# ble_car_cent_01.net
KiCad netlist of a schematic drawn in EasyEDA
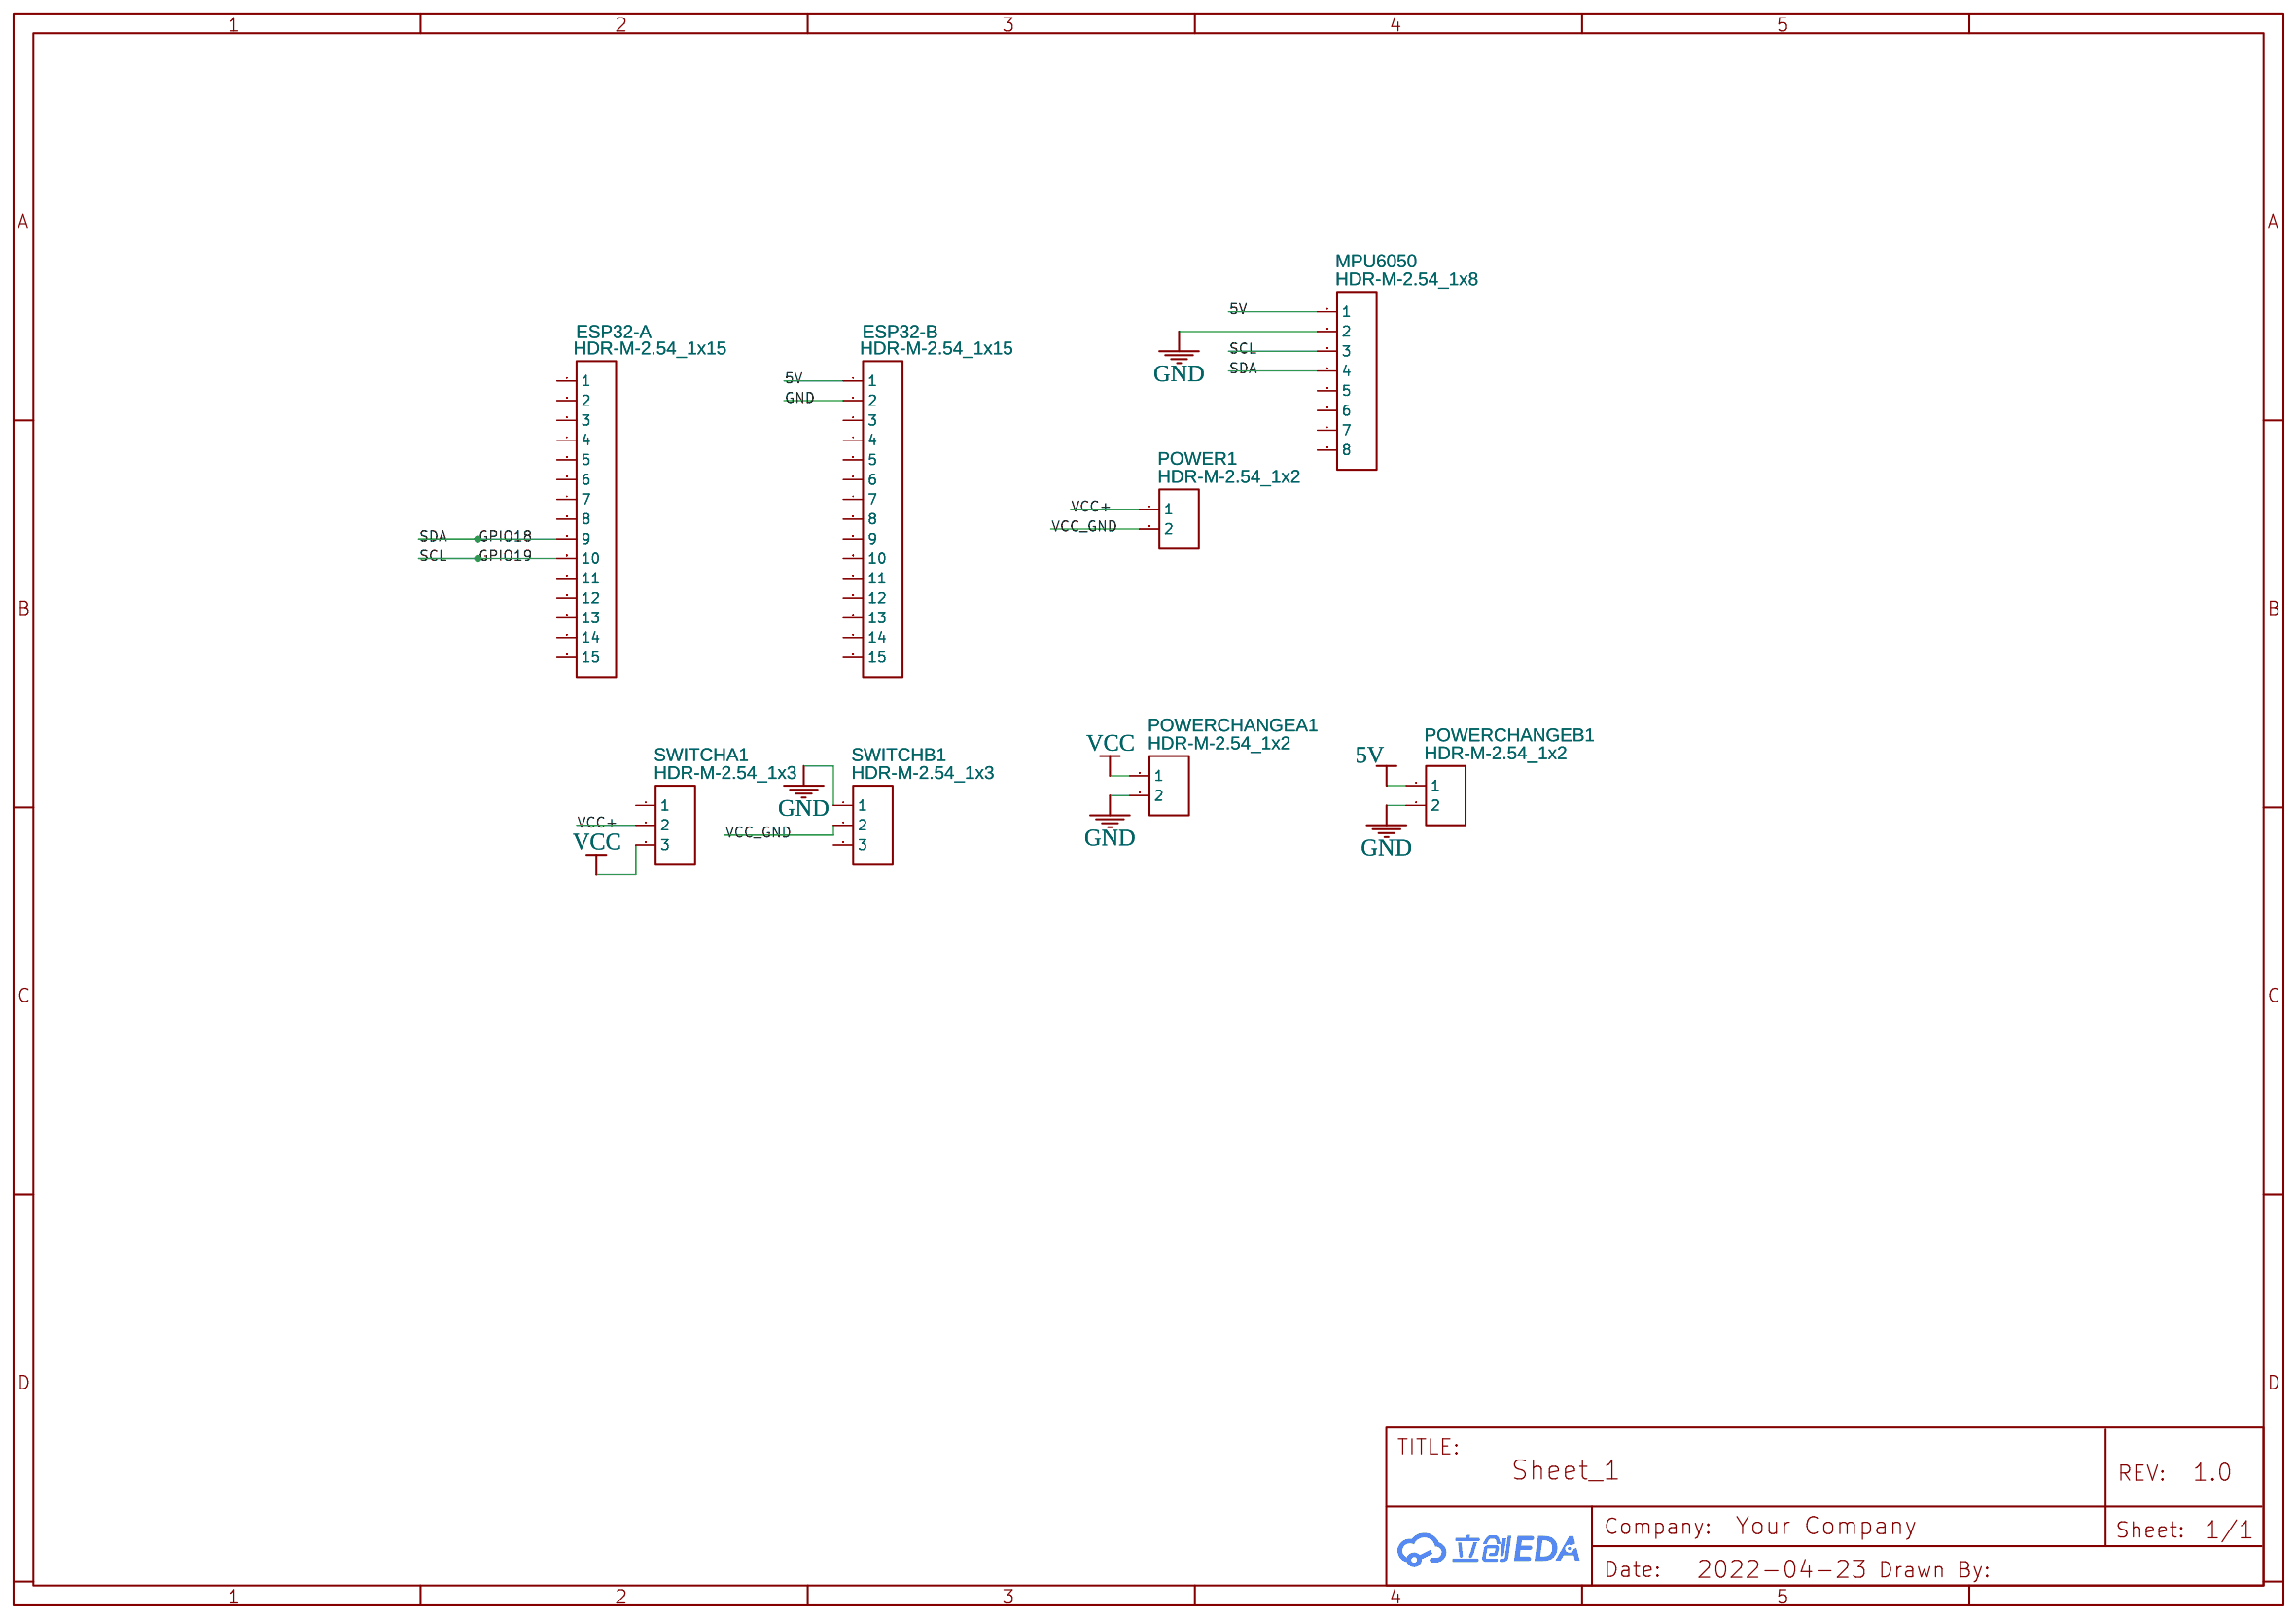
[diagram p0: schematic sheet]

(export (version "E")
  (design (tool "Eeschema 10.0.6"))
  (components
    (comp (ref "ESP32-A")
      (value "HDR-M-2.54_1x15")
      (fields (field (name "BOM_Supplier Part") "C124373"))
      (libsource (lib "") (part "HDR-M-2.54_1x15_1"))
    )
    (comp (ref "ESP32-B")
      (value "HDR-M-2.54_1x15")
      (fields (field (name "BOM_Supplier Part") "C124373"))
      (libsource (lib "") (part "HDR-M-2.54_1x15"))
    )
    (comp (ref "MPU6050")
      (value "HDR-M-2.54_1x8")
      (fields (field (name "BOM_Supplier Part") "C190820"))
      (libsource (lib "") (part "HDR-M-2.54_1x8"))
    )
    (comp (ref "POWER1")
      (value "HDR-M-2.54_1x2")
      (fields (field (name "BOM_Supplier Part") "C124375"))
      (libsource (lib "") (part "HDR-M-2.54_1x2"))
    )
    (comp (ref "POWERCHANGEA1")
      (value "HDR-M-2.54_1x2")
      (fields (field (name "BOM_Supplier Part") "C124375"))
      (libsource (lib "") (part "HDR-M-2.54_1x2_2"))
    )
    (comp (ref "POWERCHANGEB1")
      (value "HDR-M-2.54_1x2")
      (fields (field (name "BOM_Supplier Part") "C124375"))
      (libsource (lib "") (part "HDR-M-2.54_1x2_1"))
    )
    (comp (ref "SWITCHA1")
      (value "HDR-M-2.54_1x3")
      (fields (field (name "BOM_Supplier Part") "C180248"))
      (libsource (lib "") (part "HDR-M-2.54_1x3_1"))
    )
    (comp (ref "SWITCHB1")
      (value "HDR-M-2.54_1x3")
      (fields (field (name "BOM_Supplier Part") "C180248"))
      (libsource (lib "") (part "HDR-M-2.54_1x3"))
    )
  )
  (nets
    (net (code "1") (name "/GPIO18") (class "Default")
      (node (ref "ESP32-A") (pin "9") (pinfunction "9_9") (pintype "unspecified"))
      (node (ref "MPU6050") (pin "4") (pinfunction "4_4") (pintype "unspecified"))
    )
    (net (code "2") (name "/GPIO19") (class "Default")
      (node (ref "ESP32-A") (pin "10") (pinfunction "10_10") (pintype "unspecified"))
      (node (ref "MPU6050") (pin "3") (pinfunction "3_3") (pintype "unspecified"))
    )
    (net (code "3") (name "/VCC+") (class "Default")
      (node (ref "POWER1") (pin "1") (pinfunction "1_1") (pintype "unspecified"))
      (node (ref "SWITCHA1") (pin "2") (pinfunction "2_2") (pintype "input"))
    )
    (net (code "4") (name "/VCC_GND") (class "Default")
      (node (ref "POWER1") (pin "2") (pinfunction "2_2") (pintype "unspecified"))
      (node (ref "SWITCHB1") (pin "2") (pinfunction "2_2") (pintype "input"))
    )
    (net (code "5") (name "5V") (class "Default")
      (node (ref "ESP32-B") (pin "1") (pinfunction "1_1") (pintype "unspecified"))
      (node (ref "MPU6050") (pin "1") (pinfunction "1_1") (pintype "unspecified"))
      (node (ref "POWERCHANGEB1") (pin "1") (pinfunction "1_1") (pintype "unspecified"))
    )
    (net (code "6") (name "GND") (class "Default")
      (node (ref "ESP32-B") (pin "2") (pinfunction "2_2") (pintype "unspecified"))
      (node (ref "MPU6050") (pin "2") (pinfunction "2_2") (pintype "unspecified"))
      (node (ref "POWERCHANGEA1") (pin "2") (pinfunction "2_2") (pintype "unspecified"))
      (node (ref "POWERCHANGEB1") (pin "2") (pinfunction "2_2") (pintype "unspecified"))
      (node (ref "SWITCHB1") (pin "1") (pinfunction "1_1") (pintype "input"))
    )
    (net (code "7") (name "VCC") (class "Default")
      (node (ref "POWERCHANGEA1") (pin "1") (pinfunction "1_1") (pintype "unspecified"))
      (node (ref "SWITCHA1") (pin "3") (pinfunction "3_3") (pintype "input"))
    )
    (net (code "8") (name "unconnected-(ESP32-A-Pad1)") (class "Default")
      (node (ref "ESP32-A") (pin "1") (pinfunction "1_1") (pintype "unspecified"))
    )
    (net (code "9") (name "unconnected-(ESP32-A-Pad2)") (class "Default")
      (node (ref "ESP32-A") (pin "2") (pinfunction "2_2") (pintype "unspecified"))
    )
    (net (code "10") (name "unconnected-(ESP32-A-Pad3)") (class "Default")
      (node (ref "ESP32-A") (pin "3") (pinfunction "3_3") (pintype "unspecified"))
    )
    (net (code "11") (name "unconnected-(ESP32-A-Pad4)") (class "Default")
      (node (ref "ESP32-A") (pin "4") (pinfunction "4_4") (pintype "unspecified"))
    )
    (net (code "12") (name "unconnected-(ESP32-A-Pad5)") (class "Default")
      (node (ref "ESP32-A") (pin "5") (pinfunction "5_5") (pintype "unspecified"))
    )
    (net (code "13") (name "unconnected-(ESP32-A-Pad6)") (class "Default")
      (node (ref "ESP32-A") (pin "6") (pinfunction "6_6") (pintype "unspecified"))
    )
    (net (code "14") (name "unconnected-(ESP32-A-Pad7)") (class "Default")
      (node (ref "ESP32-A") (pin "7") (pinfunction "7_7") (pintype "unspecified"))
    )
    (net (code "15") (name "unconnected-(ESP32-A-Pad8)") (class "Default")
      (node (ref "ESP32-A") (pin "8") (pinfunction "8_8") (pintype "unspecified"))
    )
    (net (code "16") (name "unconnected-(ESP32-A-Pad11)") (class "Default")
      (node (ref "ESP32-A") (pin "11") (pinfunction "11_11") (pintype "unspecified"))
    )
    (net (code "17") (name "unconnected-(ESP32-A-Pad12)") (class "Default")
      (node (ref "ESP32-A") (pin "12") (pinfunction "12_12") (pintype "unspecified"))
    )
    (net (code "18") (name "unconnected-(ESP32-A-Pad13)") (class "Default")
      (node (ref "ESP32-A") (pin "13") (pinfunction "13_13") (pintype "unspecified"))
    )
    (net (code "19") (name "unconnected-(ESP32-A-Pad14)") (class "Default")
      (node (ref "ESP32-A") (pin "14") (pinfunction "14_14") (pintype "unspecified"))
    )
    (net (code "20") (name "unconnected-(ESP32-A-Pad15)") (class "Default")
      (node (ref "ESP32-A") (pin "15") (pinfunction "15_15") (pintype "unspecified"))
    )
    (net (code "21") (name "unconnected-(ESP32-B-Pad3)") (class "Default")
      (node (ref "ESP32-B") (pin "3") (pinfunction "3_3") (pintype "unspecified"))
    )
    (net (code "22") (name "unconnected-(ESP32-B-Pad4)") (class "Default")
      (node (ref "ESP32-B") (pin "4") (pinfunction "4_4") (pintype "unspecified"))
    )
    (net (code "23") (name "unconnected-(ESP32-B-Pad5)") (class "Default")
      (node (ref "ESP32-B") (pin "5") (pinfunction "5_5") (pintype "unspecified"))
    )
    (net (code "24") (name "unconnected-(ESP32-B-Pad6)") (class "Default")
      (node (ref "ESP32-B") (pin "6") (pinfunction "6_6") (pintype "unspecified"))
    )
    (net (code "25") (name "unconnected-(ESP32-B-Pad7)") (class "Default")
      (node (ref "ESP32-B") (pin "7") (pinfunction "7_7") (pintype "unspecified"))
    )
    (net (code "26") (name "unconnected-(ESP32-B-Pad8)") (class "Default")
      (node (ref "ESP32-B") (pin "8") (pinfunction "8_8") (pintype "unspecified"))
    )
    (net (code "27") (name "unconnected-(ESP32-B-Pad9)") (class "Default")
      (node (ref "ESP32-B") (pin "9") (pinfunction "9_9") (pintype "unspecified"))
    )
    (net (code "28") (name "unconnected-(ESP32-B-Pad10)") (class "Default")
      (node (ref "ESP32-B") (pin "10") (pinfunction "10_10") (pintype "unspecified"))
    )
    (net (code "29") (name "unconnected-(ESP32-B-Pad11)") (class "Default")
      (node (ref "ESP32-B") (pin "11") (pinfunction "11_11") (pintype "unspecified"))
    )
    (net (code "30") (name "unconnected-(ESP32-B-Pad12)") (class "Default")
      (node (ref "ESP32-B") (pin "12") (pinfunction "12_12") (pintype "unspecified"))
    )
    (net (code "31") (name "unconnected-(ESP32-B-Pad13)") (class "Default")
      (node (ref "ESP32-B") (pin "13") (pinfunction "13_13") (pintype "unspecified"))
    )
    (net (code "32") (name "unconnected-(ESP32-B-Pad14)") (class "Default")
      (node (ref "ESP32-B") (pin "14") (pinfunction "14_14") (pintype "unspecified"))
    )
    (net (code "33") (name "unconnected-(ESP32-B-Pad15)") (class "Default")
      (node (ref "ESP32-B") (pin "15") (pinfunction "15_15") (pintype "unspecified"))
    )
    (net (code "34") (name "unconnected-(MPU6050-Pad5)") (class "Default")
      (node (ref "MPU6050") (pin "5") (pinfunction "5_5") (pintype "unspecified"))
    )
    (net (code "35") (name "unconnected-(MPU6050-Pad6)") (class "Default")
      (node (ref "MPU6050") (pin "6") (pinfunction "6_6") (pintype "unspecified"))
    )
    (net (code "36") (name "unconnected-(MPU6050-Pad7)") (class "Default")
      (node (ref "MPU6050") (pin "7") (pinfunction "7_7") (pintype "unspecified"))
    )
    (net (code "37") (name "unconnected-(MPU6050-Pad8)") (class "Default")
      (node (ref "MPU6050") (pin "8") (pinfunction "8_8") (pintype "unspecified"))
    )
    (net (code "38") (name "unconnected-(SWITCHA1-Pad1)") (class "Default")
      (node (ref "SWITCHA1") (pin "1") (pinfunction "1_1") (pintype "input"))
    )
    (net (code "39") (name "unconnected-(SWITCHB1-Pad3)") (class "Default")
      (node (ref "SWITCHB1") (pin "3") (pinfunction "3_3") (pintype "input"))
    )
  )
)
